# schematic.net
KiCad netlist of a schematic drawn in EasyEDA
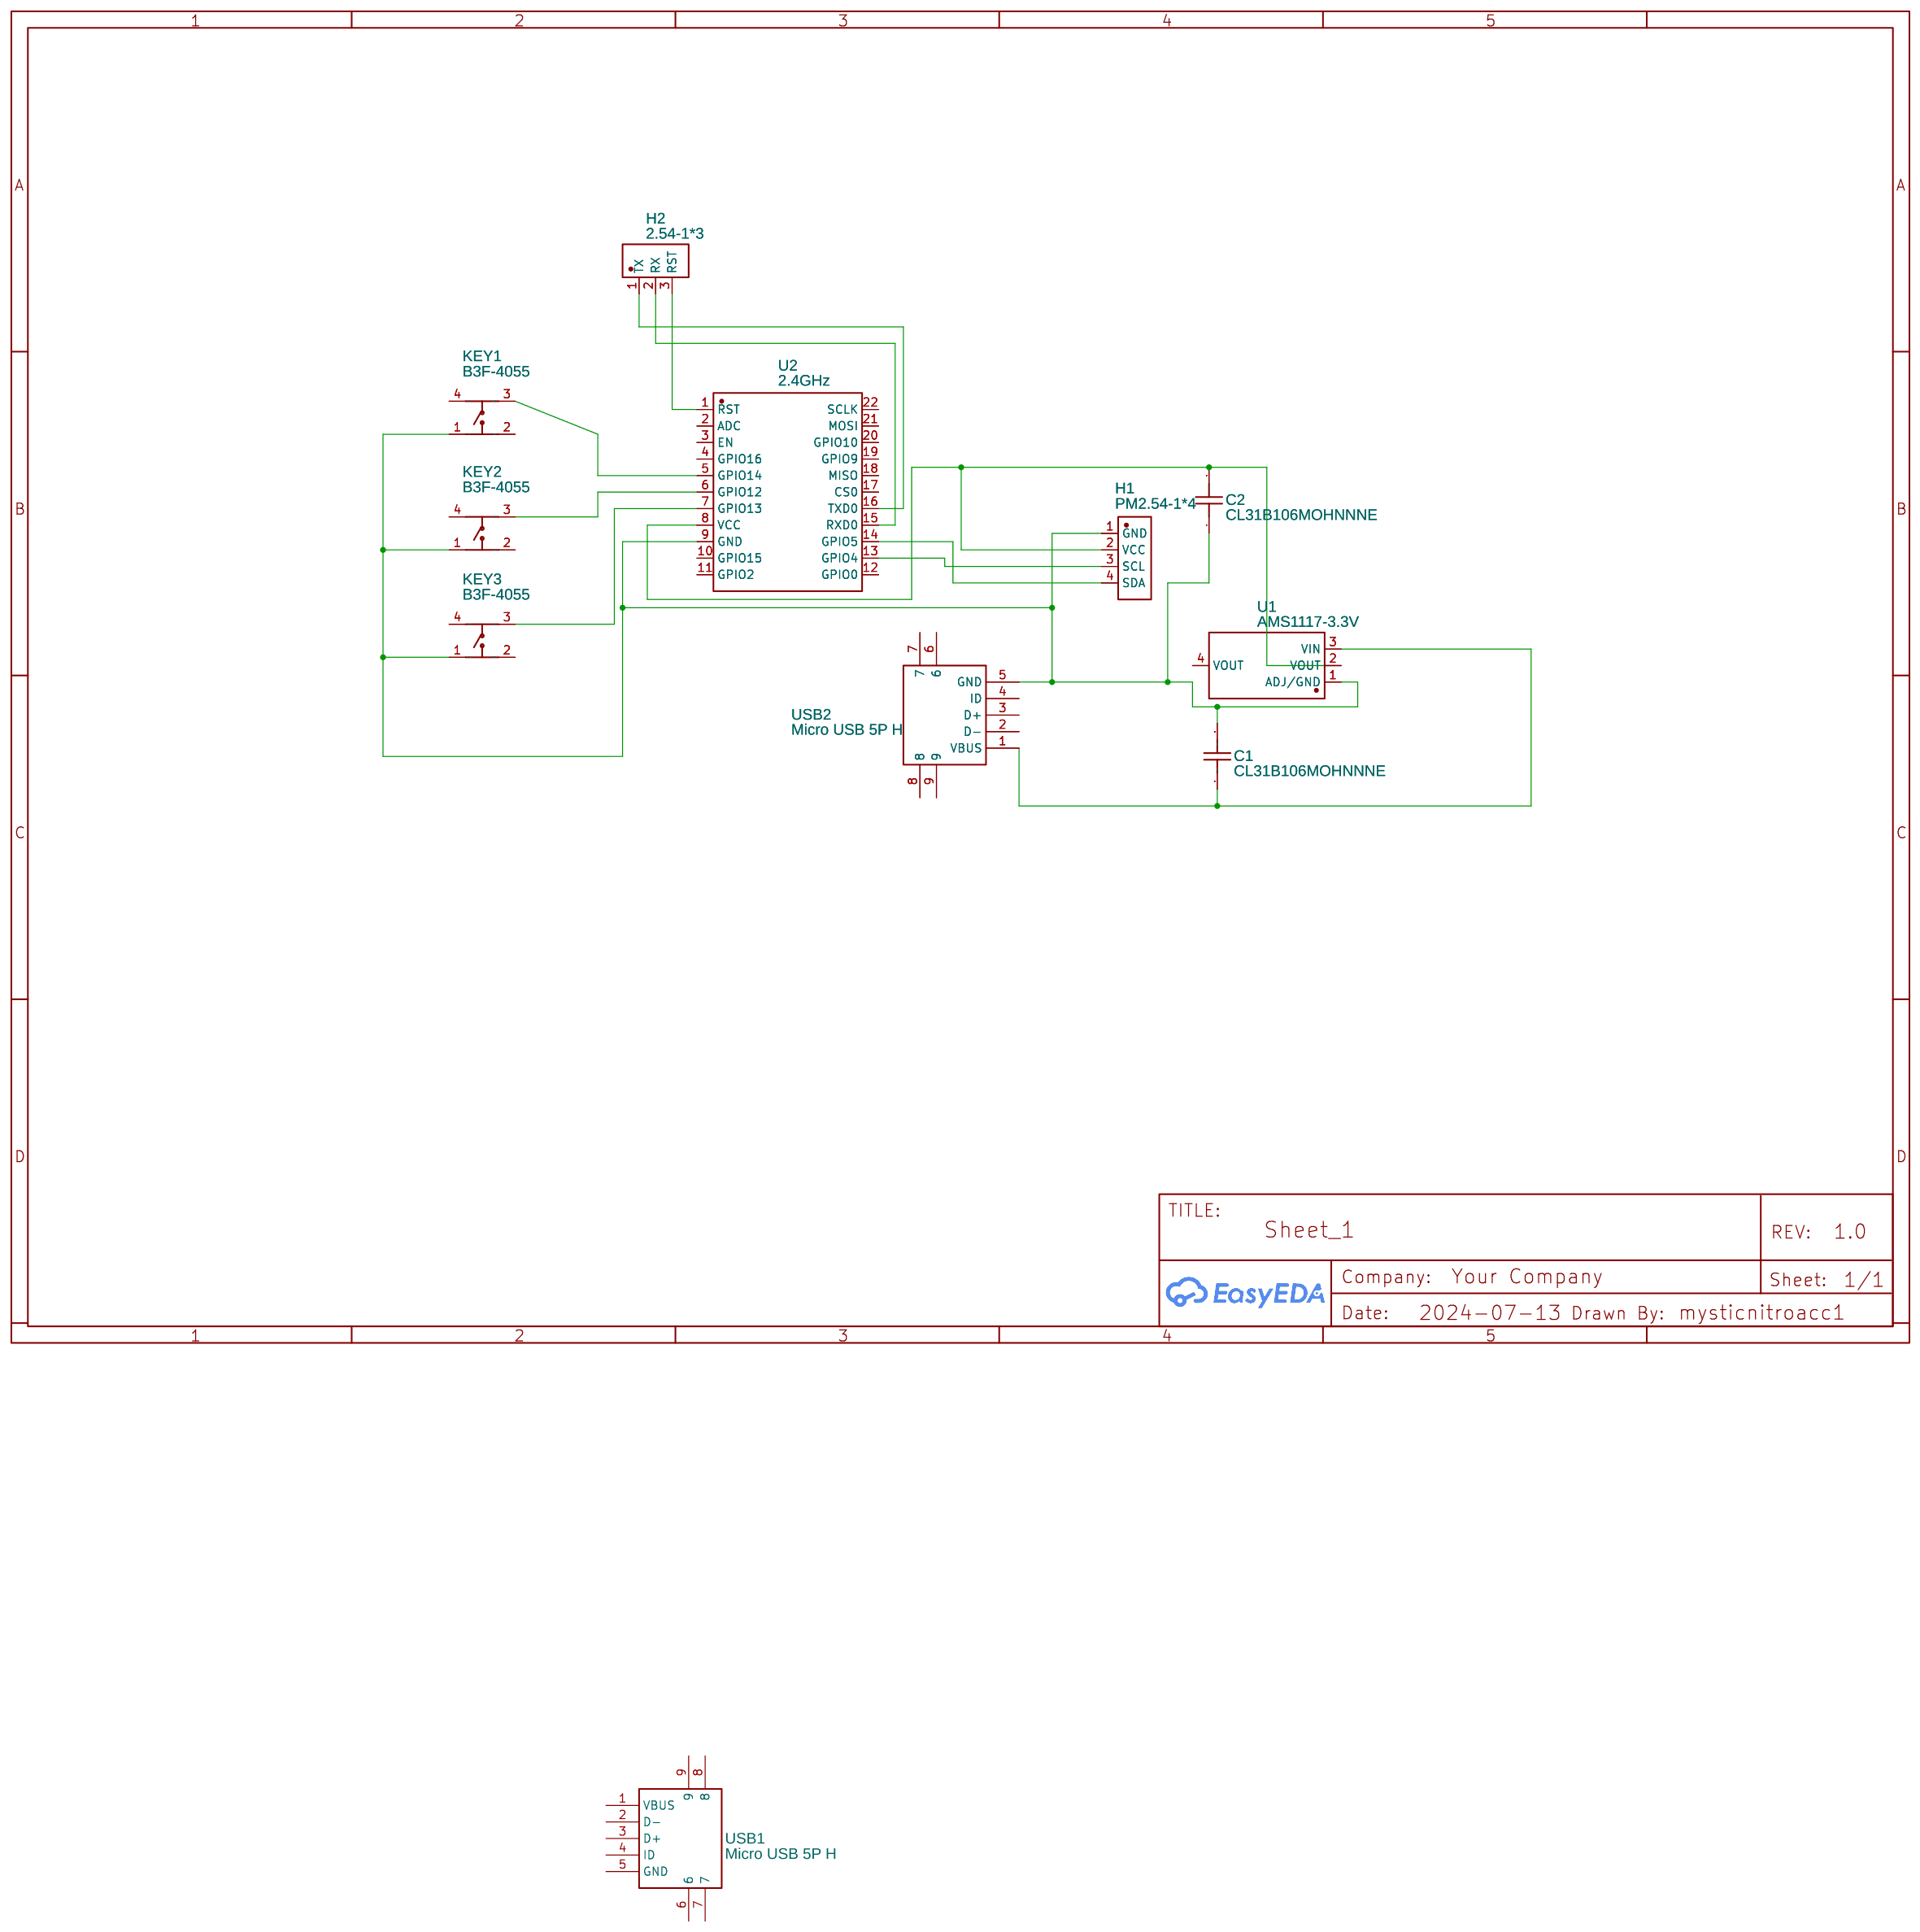
[diagram p0: schematic sheet]

(export (version "E")
  (design (tool "Eeschema 10.0.6"))
  (components
    (comp (ref "C1")
      (value "CL31B106MOHNNNE")
      (fields (field (name "Manufacturer") "Samsung Electro-Mechanics"))
      (libsource (lib "") (part "CL31B106MOHNNNE"))
    )
    (comp (ref "C2")
      (value "CL31B106MOHNNNE")
      (fields (field (name "Manufacturer") "Samsung Electro-Mechanics"))
      (libsource (lib "") (part "CL31B106MOHNNNE"))
    )
    (comp (ref "H1")
      (value "PM2.54-1*4")
      (fields (field (name "Manufacturer") "ZHOURI(洲日)"))
      (libsource (lib "") (part "PM2.54-1*4"))
    )
    (comp (ref "H2")
      (value "2.54-1*3")
      (fields (field (name "Manufacturer") "ZHOURI(洲日)"))
      (libsource (lib "") (part "2.54-1*3"))
    )
    (comp (ref "KEY1")
      (value "B3F-4055")
      (fields (field (name "Manufacturer") "OMRON(欧姆龙)"))
      (libsource (lib "") (part "B3F-4055"))
    )
    (comp (ref "KEY2")
      (value "B3F-4055")
      (fields (field (name "Manufacturer") "OMRON(欧姆龙)"))
      (libsource (lib "") (part "B3F-4055"))
    )
    (comp (ref "KEY3")
      (value "B3F-4055")
      (fields (field (name "Manufacturer") "OMRON(欧姆龙)"))
      (libsource (lib "") (part "B3F-4055"))
    )
    (comp (ref "U1")
      (value "AMS1117-3.3V")
      (fields (field (name "Manufacturer") "WPMtek(维攀)"))
      (libsource (lib "") (part "AMS1117-3.3V"))
    )
    (comp (ref "U2")
      (value "2.4GHz")
      (fields
        (field (name "Manufacturer Part") "ESP-12F(ESP8266MOD)")
        (field (name "Manufacturer") "Ai-Thinker(安信可)")
      )
      (libsource (lib "") (part "ESP-12F(ESP8266MOD)"))
    )
    (comp (ref "USB1")
      (value "Micro USB 5P H")
      (fields (field (name "Manufacturer Part") "920-E52A2021S10101") (field (name "Manufacturer") "精拓金"))
      (libsource (lib "") (part "Micro USB 5P H"))
    )
    (comp (ref "USB2")
      (value "Micro USB 5P H")
      (fields (field (name "Manufacturer Part") "920-E52A2021S10101") (field (name "Manufacturer") "精拓金"))
      (libsource (lib "") (part "Micro USB 5P H_1"))
    )
  )
  (nets
    (net (code "1") (name "Net-(H1-GND)") (class "Default")
      (node (ref "C1") (pin "2") (pinfunction "2_2") (pintype "unspecified"))
      (node (ref "C2") (pin "1") (pinfunction "1_1") (pintype "unspecified"))
      (node (ref "H1") (pin "1") (pinfunction "GND_1") (pintype "unspecified"))
      (node (ref "KEY1") (pin "1") (pinfunction "1_1") (pintype "unspecified"))
      (node (ref "KEY2") (pin "1") (pinfunction "1_1") (pintype "unspecified"))
      (node (ref "KEY3") (pin "1") (pinfunction "1_1") (pintype "unspecified"))
      (node (ref "U1") (pin "1") (pinfunction "ADJ/GND_1") (pintype "unspecified"))
      (node (ref "U2") (pin "9") (pinfunction "GND_9") (pintype "unspecified"))
      (node (ref "USB2") (pin "5") (pinfunction "GND_5") (pintype "unspecified"))
    )
    (net (code "2") (name "Net-(H1-SCL)") (class "Default")
      (node (ref "H1") (pin "3") (pinfunction "SCL_3") (pintype "unspecified"))
      (node (ref "U2") (pin "13") (pinfunction "GPIO4_13") (pintype "unspecified"))
    )
    (net (code "3") (name "Net-(H1-SDA)") (class "Default")
      (node (ref "H1") (pin "4") (pinfunction "SDA_4") (pintype "unspecified"))
      (node (ref "U2") (pin "14") (pinfunction "GPIO5_14") (pintype "unspecified"))
    )
    (net (code "4") (name "Net-(H1-VCC)") (class "Default")
      (node (ref "C2") (pin "2") (pinfunction "2_2") (pintype "unspecified"))
      (node (ref "H1") (pin "2") (pinfunction "VCC_2") (pintype "unspecified"))
      (node (ref "U1") (pin "2") (pinfunction "VOUT_2") (pintype "unspecified"))
      (node (ref "U2") (pin "8") (pinfunction "VCC_8") (pintype "unspecified"))
    )
    (net (code "5") (name "Net-(H2-RST)") (class "Default")
      (node (ref "H2") (pin "3") (pinfunction "RST_3") (pintype "unspecified"))
      (node (ref "U2") (pin "1") (pinfunction "RST_1") (pintype "unspecified"))
    )
    (net (code "6") (name "Net-(H2-RX)") (class "Default")
      (node (ref "H2") (pin "2") (pinfunction "RX_2") (pintype "unspecified"))
      (node (ref "U2") (pin "15") (pinfunction "RXD0_15") (pintype "unspecified"))
    )
    (net (code "7") (name "Net-(H2-TX)") (class "Default")
      (node (ref "H2") (pin "1") (pinfunction "TX_1") (pintype "unspecified"))
      (node (ref "U2") (pin "16") (pinfunction "TXD0_16") (pintype "unspecified"))
    )
    (net (code "8") (name "Net-(U1-VIN)") (class "Default")
      (node (ref "C1") (pin "1") (pinfunction "1_1") (pintype "unspecified"))
      (node (ref "U1") (pin "3") (pinfunction "VIN_3") (pintype "unspecified"))
      (node (ref "USB2") (pin "1") (pinfunction "VBUS_1") (pintype "unspecified"))
    )
    (net (code "9") (name "Net-(U2-GPIO12)") (class "Default")
      (node (ref "KEY2") (pin "3") (pinfunction "3_3") (pintype "unspecified"))
      (node (ref "U2") (pin "6") (pinfunction "GPIO12_6") (pintype "unspecified"))
    )
    (net (code "10") (name "Net-(U2-GPIO13)") (class "Default")
      (node (ref "KEY3") (pin "3") (pinfunction "3_3") (pintype "unspecified"))
      (node (ref "U2") (pin "7") (pinfunction "GPIO13_7") (pintype "unspecified"))
    )
    (net (code "11") (name "Net-(U2-GPIO14)") (class "Default")
      (node (ref "KEY1") (pin "3") (pinfunction "3_3") (pintype "unspecified"))
      (node (ref "U2") (pin "5") (pinfunction "GPIO14_5") (pintype "unspecified"))
    )
    (net (code "12") (name "unconnected-(KEY1-Pad2)") (class "Default")
      (node (ref "KEY1") (pin "2") (pinfunction "2_2") (pintype "unspecified"))
    )
    (net (code "13") (name "unconnected-(KEY1-Pad4)") (class "Default")
      (node (ref "KEY1") (pin "4") (pinfunction "4_4") (pintype "unspecified"))
    )
    (net (code "14") (name "unconnected-(KEY2-Pad2)") (class "Default")
      (node (ref "KEY2") (pin "2") (pinfunction "2_2") (pintype "unspecified"))
    )
    (net (code "15") (name "unconnected-(KEY2-Pad4)") (class "Default")
      (node (ref "KEY2") (pin "4") (pinfunction "4_4") (pintype "unspecified"))
    )
    (net (code "16") (name "unconnected-(KEY3-Pad2)") (class "Default")
      (node (ref "KEY3") (pin "2") (pinfunction "2_2") (pintype "unspecified"))
    )
    (net (code "17") (name "unconnected-(KEY3-Pad4)") (class "Default")
      (node (ref "KEY3") (pin "4") (pinfunction "4_4") (pintype "unspecified"))
    )
    (net (code "18") (name "unconnected-(U1-VOUT-Pad4)") (class "Default")
      (node (ref "U1") (pin "4") (pinfunction "VOUT_4") (pintype "unspecified"))
    )
    (net (code "19") (name "unconnected-(U2-ADC-Pad2)") (class "Default")
      (node (ref "U2") (pin "2") (pinfunction "ADC_2") (pintype "unspecified"))
    )
    (net (code "20") (name "unconnected-(U2-CS0-Pad17)") (class "Default")
      (node (ref "U2") (pin "17") (pinfunction "CS0_17") (pintype "unspecified"))
    )
    (net (code "21") (name "unconnected-(U2-EN-Pad3)") (class "Default")
      (node (ref "U2") (pin "3") (pinfunction "EN_3") (pintype "unspecified"))
    )
    (net (code "22") (name "unconnected-(U2-GPIO0-Pad12)") (class "Default")
      (node (ref "U2") (pin "12") (pinfunction "GPIO0_12") (pintype "unspecified"))
    )
    (net (code "23") (name "unconnected-(U2-GPIO2-Pad11)") (class "Default")
      (node (ref "U2") (pin "11") (pinfunction "GPIO2_11") (pintype "unspecified"))
    )
    (net (code "24") (name "unconnected-(U2-GPIO9-Pad19)") (class "Default")
      (node (ref "U2") (pin "19") (pinfunction "GPIO9_19") (pintype "unspecified"))
    )
    (net (code "25") (name "unconnected-(U2-GPIO10-Pad20)") (class "Default")
      (node (ref "U2") (pin "20") (pinfunction "GPIO10_20") (pintype "unspecified"))
    )
    (net (code "26") (name "unconnected-(U2-GPIO15-Pad10)") (class "Default")
      (node (ref "U2") (pin "10") (pinfunction "GPIO15_10") (pintype "unspecified"))
    )
    (net (code "27") (name "unconnected-(U2-GPIO16-Pad4)") (class "Default")
      (node (ref "U2") (pin "4") (pinfunction "GPIO16_4") (pintype "unspecified"))
    )
    (net (code "28") (name "unconnected-(U2-MISO-Pad18)") (class "Default")
      (node (ref "U2") (pin "18") (pinfunction "MISO_18") (pintype "unspecified"))
    )
    (net (code "29") (name "unconnected-(U2-MOSI-Pad21)") (class "Default")
      (node (ref "U2") (pin "21") (pinfunction "MOSI_21") (pintype "unspecified"))
    )
    (net (code "30") (name "unconnected-(U2-SCLK-Pad22)") (class "Default")
      (node (ref "U2") (pin "22") (pinfunction "SCLK_22") (pintype "unspecified"))
    )
    (net (code "31") (name "unconnected-(USB1-D+-Pad3)") (class "Default")
      (node (ref "USB1") (pin "3") (pinfunction "D+_3") (pintype "unspecified"))
    )
    (net (code "32") (name "unconnected-(USB1-D--Pad2)") (class "Default")
      (node (ref "USB1") (pin "2") (pinfunction "D-_2") (pintype "unspecified"))
    )
    (net (code "33") (name "unconnected-(USB1-GND-Pad5)") (class "Default")
      (node (ref "USB1") (pin "5") (pinfunction "GND_5") (pintype "unspecified"))
    )
    (net (code "34") (name "unconnected-(USB1-ID-Pad4)") (class "Default")
      (node (ref "USB1") (pin "4") (pinfunction "ID_4") (pintype "unspecified"))
    )
    (net (code "35") (name "unconnected-(USB1-Pad6)") (class "Default")
      (node (ref "USB1") (pin "6") (pinfunction "6_6") (pintype "unspecified"))
    )
    (net (code "36") (name "unconnected-(USB1-Pad7)") (class "Default")
      (node (ref "USB1") (pin "7") (pinfunction "7_7") (pintype "unspecified"))
    )
    (net (code "37") (name "unconnected-(USB1-Pad8)") (class "Default")
      (node (ref "USB1") (pin "8") (pinfunction "8_8") (pintype "unspecified"))
    )
    (net (code "38") (name "unconnected-(USB1-Pad9)") (class "Default")
      (node (ref "USB1") (pin "9") (pinfunction "9_9") (pintype "unspecified"))
    )
    (net (code "39") (name "unconnected-(USB1-VBUS-Pad1)") (class "Default")
      (node (ref "USB1") (pin "1") (pinfunction "VBUS_1") (pintype "unspecified"))
    )
    (net (code "40") (name "unconnected-(USB2-D+-Pad3)") (class "Default")
      (node (ref "USB2") (pin "3") (pinfunction "D+_3") (pintype "unspecified"))
    )
    (net (code "41") (name "unconnected-(USB2-D--Pad2)") (class "Default")
      (node (ref "USB2") (pin "2") (pinfunction "D-_2") (pintype "unspecified"))
    )
    (net (code "42") (name "unconnected-(USB2-ID-Pad4)") (class "Default")
      (node (ref "USB2") (pin "4") (pinfunction "ID_4") (pintype "unspecified"))
    )
    (net (code "43") (name "unconnected-(USB2-Pad6)") (class "Default")
      (node (ref "USB2") (pin "6") (pinfunction "6_6") (pintype "unspecified"))
    )
    (net (code "44") (name "unconnected-(USB2-Pad7)") (class "Default")
      (node (ref "USB2") (pin "7") (pinfunction "7_7") (pintype "unspecified"))
    )
    (net (code "45") (name "unconnected-(USB2-Pad8)") (class "Default")
      (node (ref "USB2") (pin "8") (pinfunction "8_8") (pintype "unspecified"))
    )
    (net (code "46") (name "unconnected-(USB2-Pad9)") (class "Default")
      (node (ref "USB2") (pin "9") (pinfunction "9_9") (pintype "unspecified"))
    )
  )
)
